# RS485_RS232.net
KiCad netlist of a schematic drawn in Altium Designer
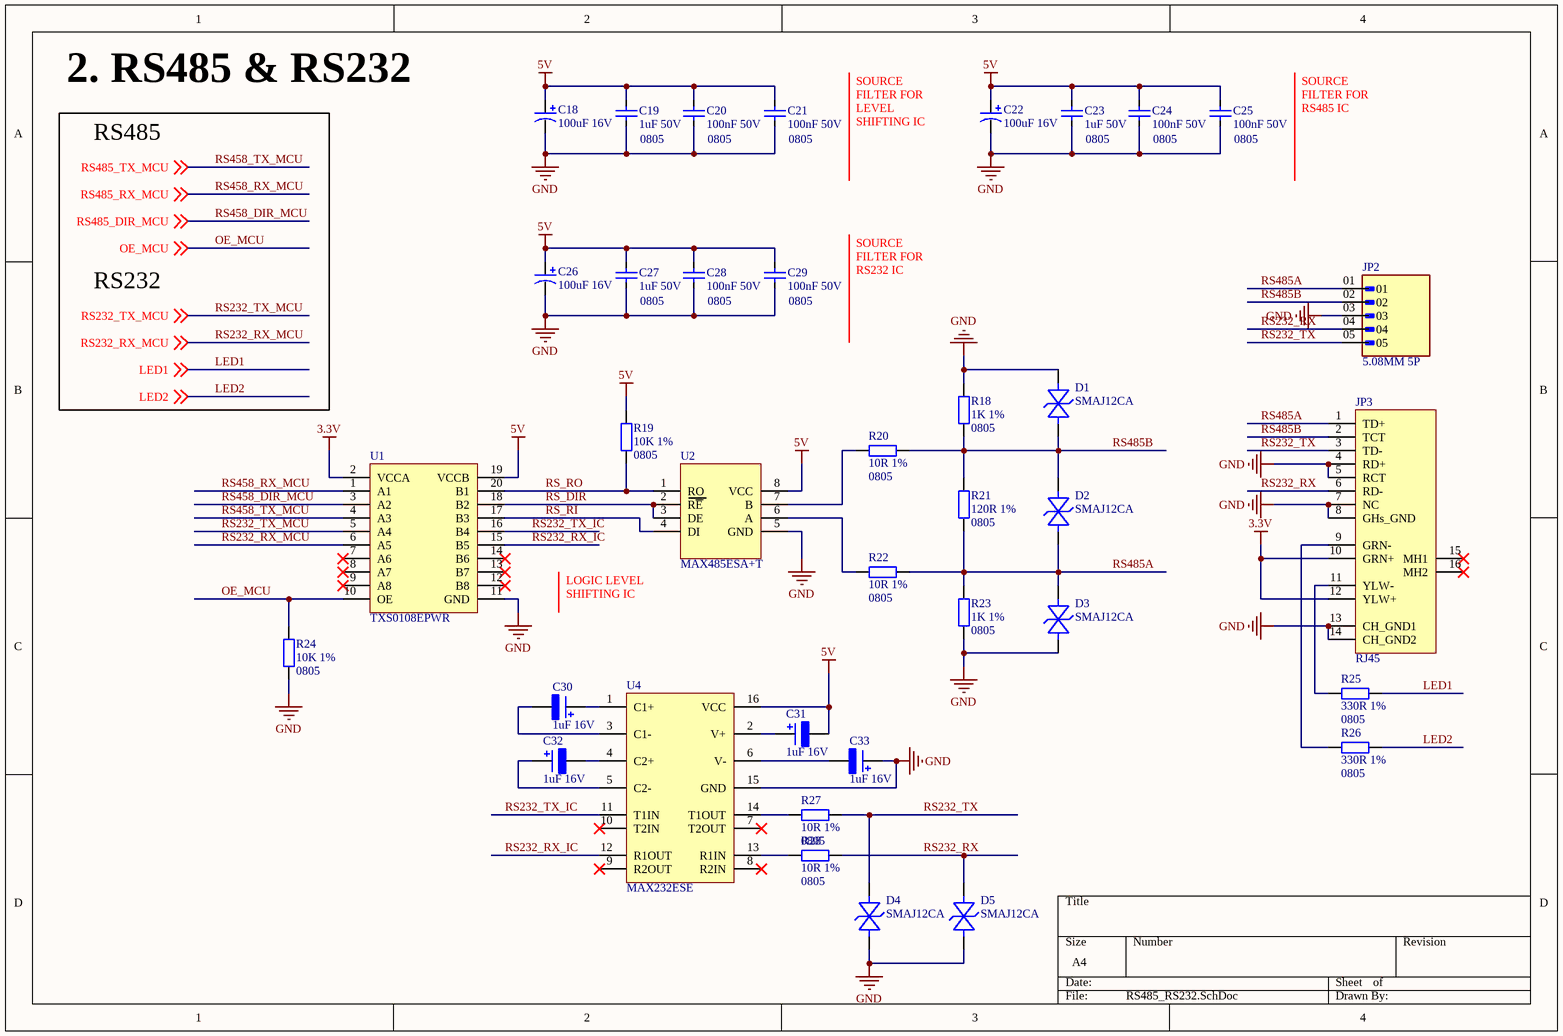
[diagram p0: RS485_RS232.SchDoc]

(export (version "E")
  (design (tool "Eeschema 10.0.6"))
  (components
    (comp (ref "C18")
      (value "100uF 16V")
      (footprint "CAP-ALU-SMD-D")
      (description "100uF 16V 63mA@120Hz ±20% SMD,D6.3xL5.4mm Aluminum Electrolytic Capacitors - SMD ROHS")
      (fields
        (field (name "MANUFACTURER") "DMBJ")
        (field (name "MANUFACTURE PART NUMBER") "RVT1C101M0605 100UF 16V")
      )
      (libsource (lib "Capacitors") (part "C_ALU_100uF_16V"))
    )
    (comp (ref "C19")
      (value "1uF 50V")
      (footprint "CAP_SMD_0805")
      (description "1 µF ±10% 50V Ceramic Capacitor X7R 0805 (2012 Metric)")
      (fields
        (field (name "MANUFACTURER") "Samsung Electro-Mechanics")
        (field (name "MANUFACTURE PART NUMBER") "CL21B105KBFNNNG")
        (field (name "SIZE") "0805")
      )
      (libsource (lib "Capacitors") (part "C0805_MLCC_1uF_50V"))
    )
    (comp (ref "C20")
      (value "100nF 50V")
      (footprint "CAP_SMD_0805")
      (description "0.1 µF ±10% 50V Ceramic Capacitor X7R 0805 (2012 Metric)")
      (fields
        (field (name "MANUFACTURER") "YAGEO")
        (field (name "MANUFACTURE PART NUMBER") "CC0805KRX7R9BB104")
        (field (name "SIZE") "0805")
      )
      (libsource (lib "Capacitors") (part "C0805_MLCC_100nF_50V"))
    )
    (comp (ref "C21")
      (value "100nF 50V")
      (footprint "CAP_SMD_0805")
      (description "0.1 µF ±10% 50V Ceramic Capacitor X7R 0805 (2012 Metric)")
      (fields
        (field (name "MANUFACTURER") "YAGEO")
        (field (name "MANUFACTURE PART NUMBER") "CC0805KRX7R9BB104")
        (field (name "SIZE") "0805")
      )
      (libsource (lib "Capacitors") (part "C0805_MLCC_100nF_50V"))
    )
    (comp (ref "C22")
      (value "100uF 16V")
      (footprint "CAP-ALU-SMD-D")
      (description "100uF 16V 63mA@120Hz ±20% SMD,D6.3xL5.4mm Aluminum Electrolytic Capacitors - SMD ROHS")
      (fields
        (field (name "MANUFACTURER") "DMBJ")
        (field (name "MANUFACTURE PART NUMBER") "RVT1C101M0605 100UF 16V")
      )
      (libsource (lib "Capacitors") (part "C_ALU_100uF_16V"))
    )
    (comp (ref "C23")
      (value "1uF 50V")
      (footprint "CAP_SMD_0805")
      (description "1 µF ±10% 50V Ceramic Capacitor X7R 0805 (2012 Metric)")
      (fields
        (field (name "MANUFACTURER") "Samsung Electro-Mechanics")
        (field (name "MANUFACTURE PART NUMBER") "CL21B105KBFNNNG")
        (field (name "SIZE") "0805")
      )
      (libsource (lib "Capacitors") (part "C0805_MLCC_1uF_50V"))
    )
    (comp (ref "C24")
      (value "100nF 50V")
      (footprint "CAP_SMD_0805")
      (description "0.1 µF ±10% 50V Ceramic Capacitor X7R 0805 (2012 Metric)")
      (fields
        (field (name "MANUFACTURER") "YAGEO")
        (field (name "MANUFACTURE PART NUMBER") "CC0805KRX7R9BB104")
        (field (name "SIZE") "0805")
      )
      (libsource (lib "Capacitors") (part "C0805_MLCC_100nF_50V"))
    )
    (comp (ref "C25")
      (value "100nF 50V")
      (footprint "CAP_SMD_0805")
      (description "0.1 µF ±10% 50V Ceramic Capacitor X7R 0805 (2012 Metric)")
      (fields
        (field (name "MANUFACTURER") "YAGEO")
        (field (name "MANUFACTURE PART NUMBER") "CC0805KRX7R9BB104")
        (field (name "SIZE") "0805")
      )
      (libsource (lib "Capacitors") (part "C0805_MLCC_100nF_50V"))
    )
    (comp (ref "C26")
      (value "100uF 16V")
      (footprint "CAP-ALU-SMD-D")
      (description "100uF 16V 63mA@120Hz ±20% SMD,D6.3xL5.4mm Aluminum Electrolytic Capacitors - SMD ROHS")
      (fields
        (field (name "MANUFACTURER") "DMBJ")
        (field (name "MANUFACTURE PART NUMBER") "RVT1C101M0605 100UF 16V")
      )
      (libsource (lib "Capacitors") (part "C_ALU_100uF_16V"))
    )
    (comp (ref "C27")
      (value "1uF 50V")
      (footprint "CAP_SMD_0805")
      (description "1 µF ±10% 50V Ceramic Capacitor X7R 0805 (2012 Metric)")
      (fields
        (field (name "MANUFACTURER") "Samsung Electro-Mechanics")
        (field (name "MANUFACTURE PART NUMBER") "CL21B105KBFNNNG")
        (field (name "SIZE") "0805")
      )
      (libsource (lib "Capacitors") (part "C0805_MLCC_1uF_50V"))
    )
    (comp (ref "C28")
      (value "100nF 50V")
      (footprint "CAP_SMD_0805")
      (description "0.1 µF ±10% 50V Ceramic Capacitor X7R 0805 (2012 Metric)")
      (fields
        (field (name "MANUFACTURER") "YAGEO")
        (field (name "MANUFACTURE PART NUMBER") "CC0805KRX7R9BB104")
        (field (name "SIZE") "0805")
      )
      (libsource (lib "Capacitors") (part "C0805_MLCC_100nF_50V"))
    )
    (comp (ref "C29")
      (value "100nF 50V")
      (footprint "CAP_SMD_0805")
      (description "0.1 µF ±10% 50V Ceramic Capacitor X7R 0805 (2012 Metric)")
      (fields
        (field (name "MANUFACTURER") "YAGEO")
        (field (name "MANUFACTURE PART NUMBER") "CC0805KRX7R9BB104")
        (field (name "SIZE") "0805")
      )
      (libsource (lib "Capacitors") (part "C0805_MLCC_100nF_50V"))
    )
    (comp (ref "C30")
      (value "1uF 16V")
      (footprint "TANTALUM_3216")
      (description "10 µF Molded Tantalum Capacitors 16 V 1210 (3528 Metric) 2.8Ohm")
      (fields (field (name "MANUFACTURER") "KEMET") (field (name "MANUFACTURE PART NUMBER") "T491A105K016AT"))
      (libsource (lib "Capacitors") (part "C3216_TAN_1uF_16V"))
    )
    (comp (ref "C31")
      (value "1uF 16V")
      (footprint "TANTALUM_3216")
      (description "10 µF Molded Tantalum Capacitors 16 V 1210 (3528 Metric) 2.8Ohm")
      (fields (field (name "MANUFACTURER") "KEMET") (field (name "MANUFACTURE PART NUMBER") "T491A105K016AT"))
      (libsource (lib "") (part "C3216_TAN_1uF_16V_1"))
    )
    (comp (ref "C32")
      (value "1uF 16V")
      (footprint "TANTALUM_3216")
      (description "10 µF Molded Tantalum Capacitors 16 V 1210 (3528 Metric) 2.8Ohm")
      (fields (field (name "MANUFACTURER") "KEMET") (field (name "MANUFACTURE PART NUMBER") "T491A105K016AT"))
      (libsource (lib "") (part "C3216_TAN_1uF_16V_1"))
    )
    (comp (ref "C33")
      (value "1uF 16V")
      (footprint "TANTALUM_3216")
      (description "10 µF Molded Tantalum Capacitors 16 V 1210 (3528 Metric) 2.8Ohm")
      (fields (field (name "MANUFACTURER") "KEMET") (field (name "MANUFACTURE PART NUMBER") "T491A105K016AT"))
      (libsource (lib "Capacitors") (part "C3216_TAN_1uF_16V"))
    )
    (comp (ref "D1")
      (value "SMAJ12CA")
      (footprint "SMA")
      (description "19.9V Clamp 20.1A Ipp Tvs Diode Surface Mount DO-214AC (SMA)")
      (fields (field (name "MANUFACTURER") "Littelfuse Inc."))
      (libsource (lib "Diode") (part "TVS_20V_SMAJ12CA"))
    )
    (comp (ref "D2")
      (value "SMAJ12CA")
      (footprint "SMA")
      (description "19.9V Clamp 20.1A Ipp Tvs Diode Surface Mount DO-214AC (SMA)")
      (fields (field (name "MANUFACTURER") "Littelfuse Inc."))
      (libsource (lib "Diode") (part "TVS_20V_SMAJ12CA"))
    )
    (comp (ref "D3")
      (value "SMAJ12CA")
      (footprint "SMA")
      (description "19.9V Clamp 20.1A Ipp Tvs Diode Surface Mount DO-214AC (SMA)")
      (fields (field (name "MANUFACTURER") "Littelfuse Inc."))
      (libsource (lib "Diode") (part "TVS_20V_SMAJ12CA"))
    )
    (comp (ref "D4")
      (value "SMAJ12CA")
      (footprint "SMA")
      (description "19.9V Clamp 20.1A Ipp Tvs Diode Surface Mount DO-214AC (SMA)")
      (fields (field (name "MANUFACTURER") "Littelfuse Inc."))
      (libsource (lib "Diode") (part "TVS_20V_SMAJ12CA"))
    )
    (comp (ref "D5")
      (value "SMAJ12CA")
      (footprint "SMA")
      (description "19.9V Clamp 20.1A Ipp Tvs Diode Surface Mount DO-214AC (SMA)")
      (fields (field (name "MANUFACTURER") "Littelfuse Inc."))
      (libsource (lib "Diode") (part "TVS_20V_SMAJ12CA"))
    )
    (comp (ref "JP2")
      (value "5.08MM 5P")
      (footprint "5.08MM 5P")
      (fields
        (field (name "MANUFACTURER") "Phoenix Contact")
        (field (name "MANUFACTURE PART NUMBER") "1759046")
      )
      (libsource (lib "Connectors") (part "TERMINAL_5.08MM_5P"))
    )
    (comp (ref "JP3")
      (value "RJ45")
      (footprint "RJ 45")
      (description "1 Port RJ45Through Hole 10/100 Base-T, AutoMDIX")
      (fields (field (name "MANUFACTURER") "WIZnet") (field (name "MANUFACTURE PART NUMBER") "1278-1052-ND"))
      (libsource (lib "Connectors") (part "RJ45"))
    )
    (comp (ref "R18")
      (value "1K 1%")
      (footprint "RES_SMD_0805")
      (description "1 kOhms ±1% 0.125W, 1/8W Chip Resistor 0805 (2012 Metric) Moisture Resistant Thick Film")
      (fields
        (field (name "MANUFACTURER") "YAGEO")
        (field (name "MANUFACTURE PART NUMBER") "311-1.00KCRCT-ND")
        (field (name "SIZE") "0805")
      )
      (libsource (lib "Resistors") (part "R0805_1K"))
    )
    (comp (ref "R19")
      (value "10K 1%")
      (footprint "RES_SMD_0805")
      (description "10 kOhms ±1% 0.125W, 1/8W Chip Resistor 0805 (2012 Metric) Moisture Resistant Thick Film")
      (fields
        (field (name "MANUFACTURER") "YAGEO")
        (field (name "MANUFACTURE PART NUMBER") "RC0805FR-0710KL")
        (field (name "SIZE") "0805")
      )
      (libsource (lib "Resistors") (part "R0805_10K"))
    )
    (comp (ref "R20")
      (value "10R 1%")
      (footprint "RES_SMD_0805")
      (description "10 Ohms ±1% 0.125W, 1/8W Chip Resistor 0805 (2012 Metric) Moisture Resistant Thick Film")
      (fields
        (field (name "MANUFACTURER") "YAGEO")
        (field (name "MANUFACTURE PART NUMBER") "RC0805FR-0710RL")
        (field (name "SIZE") "0805")
      )
      (libsource (lib "Resistors") (part "R0805_10R"))
    )
    (comp (ref "R21")
      (value "120R 1%")
      (footprint "RES_SMD_0805")
      (description "120 Ohms ±1% 0.125W, 1/8W Chip Resistor 0805 (2012 Metric) Automotive AEC-Q200 Thick Film")
      (fields
        (field (name "MANUFACTURER") "Stackpole Electronics Inc")
        (field (name "MANUFACTURE PART NUMBER") "RMCF0805FT120R")
        (field (name "SIZE") "0805")
      )
      (libsource (lib "Resistors") (part "R0805_120R"))
    )
    (comp (ref "R22")
      (value "10R 1%")
      (footprint "RES_SMD_0805")
      (description "10 Ohms ±1% 0.125W, 1/8W Chip Resistor 0805 (2012 Metric) Moisture Resistant Thick Film")
      (fields
        (field (name "MANUFACTURER") "YAGEO")
        (field (name "MANUFACTURE PART NUMBER") "RC0805FR-0710RL")
        (field (name "SIZE") "0805")
      )
      (libsource (lib "Resistors") (part "R0805_10R"))
    )
    (comp (ref "R23")
      (value "1K 1%")
      (footprint "RES_SMD_0805")
      (description "1 kOhms ±1% 0.125W, 1/8W Chip Resistor 0805 (2012 Metric) Moisture Resistant Thick Film")
      (fields
        (field (name "MANUFACTURER") "YAGEO")
        (field (name "MANUFACTURE PART NUMBER") "311-1.00KCRCT-ND")
        (field (name "SIZE") "0805")
      )
      (libsource (lib "Resistors") (part "R0805_1K"))
    )
    (comp (ref "R24")
      (value "10K 1%")
      (footprint "RES_SMD_0805")
      (description "10 kOhms ±1% 0.125W, 1/8W Chip Resistor 0805 (2012 Metric) Moisture Resistant Thick Film")
      (fields
        (field (name "MANUFACTURER") "YAGEO")
        (field (name "MANUFACTURE PART NUMBER") "RC0805FR-0710KL")
        (field (name "SIZE") "0805")
      )
      (libsource (lib "Resistors") (part "R0805_10K"))
    )
    (comp (ref "R25")
      (value "330R 1%")
      (footprint "RES_SMD_0805")
      (description "330 Ohms ±1% 0.125W, 1/8W Chip Resistor 0805 (2012 Metric) Automotive AEC-Q200 Thick Film")
      (fields
        (field (name "MANUFACTURER") "Stackpole Electronics Inc")
        (field (name "MANUFACTURE PART NUMBER") "RMCF0805FT330R")
        (field (name "SIZE") "0805")
      )
      (libsource (lib "Resistors") (part "R0805_330R"))
    )
    (comp (ref "R26")
      (value "330R 1%")
      (footprint "RES_SMD_0805")
      (description "330 Ohms ±1% 0.125W, 1/8W Chip Resistor 0805 (2012 Metric) Automotive AEC-Q200 Thick Film")
      (fields
        (field (name "MANUFACTURER") "Stackpole Electronics Inc")
        (field (name "MANUFACTURE PART NUMBER") "RMCF0805FT330R")
        (field (name "SIZE") "0805")
      )
      (libsource (lib "Resistors") (part "R0805_330R"))
    )
    (comp (ref "R27")
      (value "10R 1%")
      (footprint "RES_SMD_0805")
      (description "10 Ohms ±1% 0.125W, 1/8W Chip Resistor 0805 (2012 Metric) Moisture Resistant Thick Film")
      (fields
        (field (name "MANUFACTURER") "YAGEO")
        (field (name "MANUFACTURE PART NUMBER") "RC0805FR-0710RL")
        (field (name "SIZE") "0805")
      )
      (libsource (lib "Resistors") (part "R0805_10R"))
    )
    (comp (ref "R28")
      (value "10R 1%")
      (footprint "RES_SMD_0805")
      (description "10 Ohms ±1% 0.125W, 1/8W Chip Resistor 0805 (2012 Metric) Moisture Resistant Thick Film")
      (fields
        (field (name "MANUFACTURER") "YAGEO")
        (field (name "MANUFACTURE PART NUMBER") "RC0805FR-0710RL")
        (field (name "SIZE") "0805")
      )
      (libsource (lib "Resistors") (part "R0805_10R"))
    )
    (comp (ref "U1")
      (value "TXS0108EPWR")
      (footprint "20-TSSOP")
      (description "Voltage Level Translator Bidirectional 1 Circuit 8 Channel 60Mbps 20-TSSOP")
      (fields (field (name "MANUFACTURER") "Texas Instruments"))
      (libsource (lib "ICs") (part "TXS0108EPWR"))
    )
    (comp (ref "U2")
      (value "MAX485ESA+T")
      (footprint "SOIC-8")
      (description "RS-422/RS-485 Interface IC Low-Power, Slew-Rate-Limited RS-485/RS-4")
      (fields (field (name "MANUFACTURER") "Analog Devices / Maxim Integrated"))
      (libsource (lib "ICs") (part "MAX485ESA+T"))
    )
    (comp (ref "U4")
      (value "MAX232ESE")
      (footprint "SOP-16")
      (description "2/2 Transceiver Full RS232 16-SOP")
      (fields (field (name "MANUFACTURER") "UMW"))
      (libsource (lib "ICs") (part "MAX232ESE"))
    )
  )
  (nets
    (net (code "1") (name "/RS232_RX") (class "Default")
      (node (ref "D5") (pin "A") (pinfunction "A_A") (pintype "passive"))
      (node (ref "JP2") (pin "04") (pinfunction "04_04") (pintype "passive"))
      (node (ref "JP3") (pin "6") (pinfunction "RD-_6") (pintype "passive"))
      (node (ref "R28") (pin "2") (pinfunction "2_2") (pintype "passive"))
    )
    (net (code "2") (name "/RS232_RX_IC") (class "Default")
      (node (ref "U1") (pin "15") (pinfunction "B5_15") (pintype "passive"))
      (node (ref "U4") (pin "12") (pinfunction "R1OUT_12") (pintype "passive"))
    )
    (net (code "3") (name "/RS232_TX") (class "Default")
      (node (ref "D4") (pin "A") (pinfunction "A_A") (pintype "passive"))
      (node (ref "JP2") (pin "05") (pinfunction "05_05") (pintype "passive"))
      (node (ref "JP3") (pin "3") (pinfunction "TD-_3") (pintype "passive"))
      (node (ref "R27") (pin "2") (pinfunction "2_2") (pintype "passive"))
    )
    (net (code "4") (name "/RS232_TX_IC") (class "Default")
      (node (ref "U1") (pin "16") (pinfunction "B4_16") (pintype "passive"))
      (node (ref "U4") (pin "11") (pinfunction "T1IN_11") (pintype "passive"))
    )
    (net (code "5") (name "/RS485A") (class "Default")
      (node (ref "D2") (pin "C") (pinfunction "C_C") (pintype "passive"))
      (node (ref "D3") (pin "A") (pinfunction "A_A") (pintype "passive"))
      (node (ref "JP2") (pin "01") (pinfunction "01_01") (pintype "passive"))
      (node (ref "JP3") (pin "1") (pinfunction "TD+_1") (pintype "passive"))
      (node (ref "R21") (pin "1") (pinfunction "1_1") (pintype "passive"))
      (node (ref "R22") (pin "2") (pinfunction "2_2") (pintype "passive"))
      (node (ref "R23") (pin "2") (pinfunction "2_2") (pintype "passive"))
    )
    (net (code "6") (name "/RS485B") (class "Default")
      (node (ref "D1") (pin "C") (pinfunction "C_C") (pintype "passive"))
      (node (ref "D2") (pin "A") (pinfunction "A_A") (pintype "passive"))
      (node (ref "JP2") (pin "02") (pinfunction "02_02") (pintype "passive"))
      (node (ref "JP3") (pin "2") (pinfunction "TCT_2") (pintype "passive"))
      (node (ref "R18") (pin "1") (pinfunction "1_1") (pintype "passive"))
      (node (ref "R20") (pin "2") (pinfunction "2_2") (pintype "passive"))
      (node (ref "R21") (pin "2") (pinfunction "2_2") (pintype "passive"))
    )
    (net (code "7") (name "/RS_DIR") (class "Default")
      (node (ref "U1") (pin "18") (pinfunction "B2_18") (pintype "passive"))
      (node (ref "U2") (pin "2") (pinfunction "R~{E}_2") (pintype "passive"))
      (node (ref "U2") (pin "3") (pinfunction "DE_3") (pintype "passive"))
    )
    (net (code "8") (name "/RS_RI") (class "Default")
      (node (ref "U1") (pin "17") (pinfunction "B3_17") (pintype "passive"))
      (node (ref "U2") (pin "4") (pinfunction "DI_4") (pintype "passive"))
    )
    (net (code "9") (name "/RS_RO") (class "Default")
      (node (ref "R19") (pin "1") (pinfunction "1_1") (pintype "passive"))
      (node (ref "U1") (pin "20") (pinfunction "B1_20") (pintype "passive"))
      (node (ref "U2") (pin "1") (pinfunction "RO_1") (pintype "passive"))
    )
    (net (code "10") (name "3.3V") (class "Default")
      (node (ref "JP3") (pin "10") (pinfunction "GRN+_10") (pintype "passive"))
      (node (ref "JP3") (pin "12") (pinfunction "YLW+_12") (pintype "passive"))
      (node (ref "U1") (pin "2") (pinfunction "VCCA_2") (pintype "passive"))
    )
    (net (code "11") (name "5V") (class "Default")
      (node (ref "C18") (pin "1") (pinfunction "1_1") (pintype "passive"))
      (node (ref "C19") (pin "1") (pinfunction "1_1") (pintype "passive"))
      (node (ref "C20") (pin "2") (pinfunction "2_2") (pintype "passive"))
      (node (ref "C21") (pin "2") (pinfunction "2_2") (pintype "passive"))
      (node (ref "C22") (pin "1") (pinfunction "1_1") (pintype "passive"))
      (node (ref "C23") (pin "1") (pinfunction "1_1") (pintype "passive"))
      (node (ref "C24") (pin "2") (pinfunction "2_2") (pintype "passive"))
      (node (ref "C25") (pin "2") (pinfunction "2_2") (pintype "passive"))
      (node (ref "C26") (pin "1") (pinfunction "1_1") (pintype "passive"))
      (node (ref "C27") (pin "1") (pinfunction "1_1") (pintype "passive"))
      (node (ref "C28") (pin "2") (pinfunction "2_2") (pintype "passive"))
      (node (ref "C29") (pin "2") (pinfunction "2_2") (pintype "passive"))
      (node (ref "C31") (pin "2") (pinfunction "2_2") (pintype "passive"))
      (node (ref "R19") (pin "2") (pinfunction "2_2") (pintype "passive"))
      (node (ref "U1") (pin "19") (pinfunction "VCCB_19") (pintype "passive"))
      (node (ref "U2") (pin "8") (pinfunction "VCC_8") (pintype "passive"))
      (node (ref "U4") (pin "16") (pinfunction "VCC_16") (pintype "passive"))
    )
    (net (code "12") (name "GND") (class "Default")
      (node (ref "C18") (pin "2") (pinfunction "2_2") (pintype "passive"))
      (node (ref "C19") (pin "2") (pinfunction "2_2") (pintype "passive"))
      (node (ref "C20") (pin "1") (pinfunction "1_1") (pintype "passive"))
      (node (ref "C21") (pin "1") (pinfunction "1_1") (pintype "passive"))
      (node (ref "C22") (pin "2") (pinfunction "2_2") (pintype "passive"))
      (node (ref "C23") (pin "2") (pinfunction "2_2") (pintype "passive"))
      (node (ref "C24") (pin "1") (pinfunction "1_1") (pintype "passive"))
      (node (ref "C25") (pin "1") (pinfunction "1_1") (pintype "passive"))
      (node (ref "C26") (pin "2") (pinfunction "2_2") (pintype "passive"))
      (node (ref "C27") (pin "2") (pinfunction "2_2") (pintype "passive"))
      (node (ref "C28") (pin "1") (pinfunction "1_1") (pintype "passive"))
      (node (ref "C29") (pin "1") (pinfunction "1_1") (pintype "passive"))
      (node (ref "C33") (pin "1") (pinfunction "1_1") (pintype "passive"))
      (node (ref "D1") (pin "A") (pinfunction "A_A") (pintype "passive"))
      (node (ref "D3") (pin "C") (pinfunction "C_C") (pintype "passive"))
      (node (ref "D4") (pin "C") (pinfunction "C_C") (pintype "passive"))
      (node (ref "D5") (pin "C") (pinfunction "C_C") (pintype "passive"))
      (node (ref "JP2") (pin "03") (pinfunction "03_03") (pintype "passive"))
      (node (ref "JP3") (pin "13") (pinfunction "CH_GND1_13") (pintype "passive"))
      (node (ref "JP3") (pin "14") (pinfunction "CH_GND2_14") (pintype "passive"))
      (node (ref "JP3") (pin "4") (pinfunction "RD+_4") (pintype "passive"))
      (node (ref "JP3") (pin "5") (pinfunction "RCT_5") (pintype "passive"))
      (node (ref "JP3") (pin "7") (pinfunction "NC_7") (pintype "passive"))
      (node (ref "JP3") (pin "8") (pinfunction "GHs_GND_8") (pintype "passive"))
      (node (ref "R18") (pin "2") (pinfunction "2_2") (pintype "passive"))
      (node (ref "R23") (pin "1") (pinfunction "1_1") (pintype "passive"))
      (node (ref "R24") (pin "1") (pinfunction "1_1") (pintype "passive"))
      (node (ref "U1") (pin "11") (pinfunction "GND_11") (pintype "passive"))
      (node (ref "U2") (pin "5") (pinfunction "GND_5") (pintype "passive"))
      (node (ref "U4") (pin "15") (pinfunction "GND_15") (pintype "passive"))
    )
    (net (code "13") (name "LED1") (class "Default")
      (node (ref "R25") (pin "2") (pinfunction "2_2") (pintype "passive"))
    )
    (net (code "14") (name "LED2") (class "Default")
      (node (ref "R26") (pin "2") (pinfunction "2_2") (pintype "passive"))
    )
    (net (code "15") (name "Net-(JP3-GRN-)") (class "Default")
      (node (ref "JP3") (pin "9") (pinfunction "GRN-_9") (pintype "passive"))
      (node (ref "R26") (pin "1") (pinfunction "1_1") (pintype "passive"))
    )
    (net (code "16") (name "Net-(JP3-YLW-)") (class "Default")
      (node (ref "JP3") (pin "11") (pinfunction "YLW-_11") (pintype "passive"))
      (node (ref "R25") (pin "1") (pinfunction "1_1") (pintype "passive"))
    )
    (net (code "17") (name "Net-(U2-A)") (class "Default")
      (node (ref "R22") (pin "1") (pinfunction "1_1") (pintype "passive"))
      (node (ref "U2") (pin "6") (pinfunction "A_6") (pintype "passive"))
    )
    (net (code "18") (name "Net-(U2-B)") (class "Default")
      (node (ref "R20") (pin "1") (pinfunction "1_1") (pintype "passive"))
      (node (ref "U2") (pin "7") (pinfunction "B_7") (pintype "passive"))
    )
    (net (code "19") (name "Net-(U4-C1+)") (class "Default")
      (node (ref "C30") (pin "1") (pinfunction "1_1") (pintype "passive"))
      (node (ref "U4") (pin "1") (pinfunction "C1+_1") (pintype "passive"))
    )
    (net (code "20") (name "Net-(U4-C1-)") (class "Default")
      (node (ref "C30") (pin "2") (pinfunction "2_2") (pintype "passive"))
      (node (ref "U4") (pin "3") (pinfunction "C1-_3") (pintype "passive"))
    )
    (net (code "21") (name "Net-(U4-C2+)") (class "Default")
      (node (ref "C32") (pin "2") (pinfunction "2_2") (pintype "passive"))
      (node (ref "U4") (pin "4") (pinfunction "C2+_4") (pintype "passive"))
    )
    (net (code "22") (name "Net-(U4-C2-)") (class "Default")
      (node (ref "C32") (pin "1") (pinfunction "1_1") (pintype "passive"))
      (node (ref "U4") (pin "5") (pinfunction "C2-_5") (pintype "passive"))
    )
    (net (code "23") (name "Net-(U4-R1IN)") (class "Default")
      (node (ref "R28") (pin "1") (pinfunction "1_1") (pintype "passive"))
      (node (ref "U4") (pin "13") (pinfunction "R1IN_13") (pintype "passive"))
    )
    (net (code "24") (name "Net-(U4-T1OUT)") (class "Default")
      (node (ref "R27") (pin "1") (pinfunction "1_1") (pintype "passive"))
      (node (ref "U4") (pin "14") (pinfunction "T1OUT_14") (pintype "passive"))
    )
    (net (code "25") (name "Net-(U4-V+)") (class "Default")
      (node (ref "C31") (pin "1") (pinfunction "1_1") (pintype "passive"))
      (node (ref "U4") (pin "2") (pinfunction "V+_2") (pintype "passive"))
    )
    (net (code "26") (name "Net-(U4-V-)") (class "Default")
      (node (ref "C33") (pin "2") (pinfunction "2_2") (pintype "passive"))
      (node (ref "U4") (pin "6") (pinfunction "V-_6") (pintype "passive"))
    )
    (net (code "27") (name "OE_MCU") (class "Default")
      (node (ref "R24") (pin "2") (pinfunction "2_2") (pintype "passive"))
      (node (ref "U1") (pin "10") (pinfunction "OE_10") (pintype "passive"))
    )
    (net (code "28") (name "RS232_RX_MCU") (class "Default")
      (node (ref "U1") (pin "6") (pinfunction "A5_6") (pintype "passive"))
    )
    (net (code "29") (name "RS232_TX_MCU") (class "Default")
      (node (ref "U1") (pin "5") (pinfunction "A4_5") (pintype "passive"))
    )
    (net (code "30") (name "RS485_DIR_MCU") (class "Default")
      (node (ref "U1") (pin "3") (pinfunction "A2_3") (pintype "passive"))
    )
    (net (code "31") (name "RS485_RX_MCU") (class "Default")
      (node (ref "U1") (pin "1") (pinfunction "A1_1") (pintype "passive"))
    )
    (net (code "32") (name "RS485_TX_MCU") (class "Default")
      (node (ref "U1") (pin "4") (pinfunction "A3_4") (pintype "passive"))
    )
    (net (code "33") (name "unconnected-(JP3-MH1-Pad15)") (class "Default")
      (node (ref "JP3") (pin "15") (pinfunction "MH1_15") (pintype "passive+no_connect"))
    )
    (net (code "34") (name "unconnected-(JP3-MH2-Pad16)") (class "Default")
      (node (ref "JP3") (pin "16") (pinfunction "MH2_16") (pintype "passive+no_connect"))
    )
    (net (code "35") (name "unconnected-(U1-A6-Pad7)") (class "Default")
      (node (ref "U1") (pin "7") (pinfunction "A6_7") (pintype "passive+no_connect"))
    )
    (net (code "36") (name "unconnected-(U1-A7-Pad8)") (class "Default")
      (node (ref "U1") (pin "8") (pinfunction "A7_8") (pintype "passive+no_connect"))
    )
    (net (code "37") (name "unconnected-(U1-A8-Pad9)") (class "Default")
      (node (ref "U1") (pin "9") (pinfunction "A8_9") (pintype "passive+no_connect"))
    )
    (net (code "38") (name "unconnected-(U1-B6-Pad14)") (class "Default")
      (node (ref "U1") (pin "14") (pinfunction "B6_14") (pintype "passive+no_connect"))
    )
    (net (code "39") (name "unconnected-(U1-B7-Pad13)") (class "Default")
      (node (ref "U1") (pin "13") (pinfunction "B7_13") (pintype "passive+no_connect"))
    )
    (net (code "40") (name "unconnected-(U1-B8-Pad12)") (class "Default")
      (node (ref "U1") (pin "12") (pinfunction "B8_12") (pintype "passive+no_connect"))
    )
    (net (code "41") (name "unconnected-(U4-R2IN-Pad8)") (class "Default")
      (node (ref "U4") (pin "8") (pinfunction "R2IN_8") (pintype "passive+no_connect"))
    )
    (net (code "42") (name "unconnected-(U4-R2OUT-Pad9)") (class "Default")
      (node (ref "U4") (pin "9") (pinfunction "R2OUT_9") (pintype "passive+no_connect"))
    )
    (net (code "43") (name "unconnected-(U4-T2IN-Pad10)") (class "Default")
      (node (ref "U4") (pin "10") (pinfunction "T2IN_10") (pintype "passive+no_connect"))
    )
    (net (code "44") (name "unconnected-(U4-T2OUT-Pad7)") (class "Default")
      (node (ref "U4") (pin "7") (pinfunction "T2OUT_7") (pintype "passive+no_connect"))
    )
  )
)
